# complete_system_Rev_A.net
KiCad netlist of a schematic drawn in EAGLE
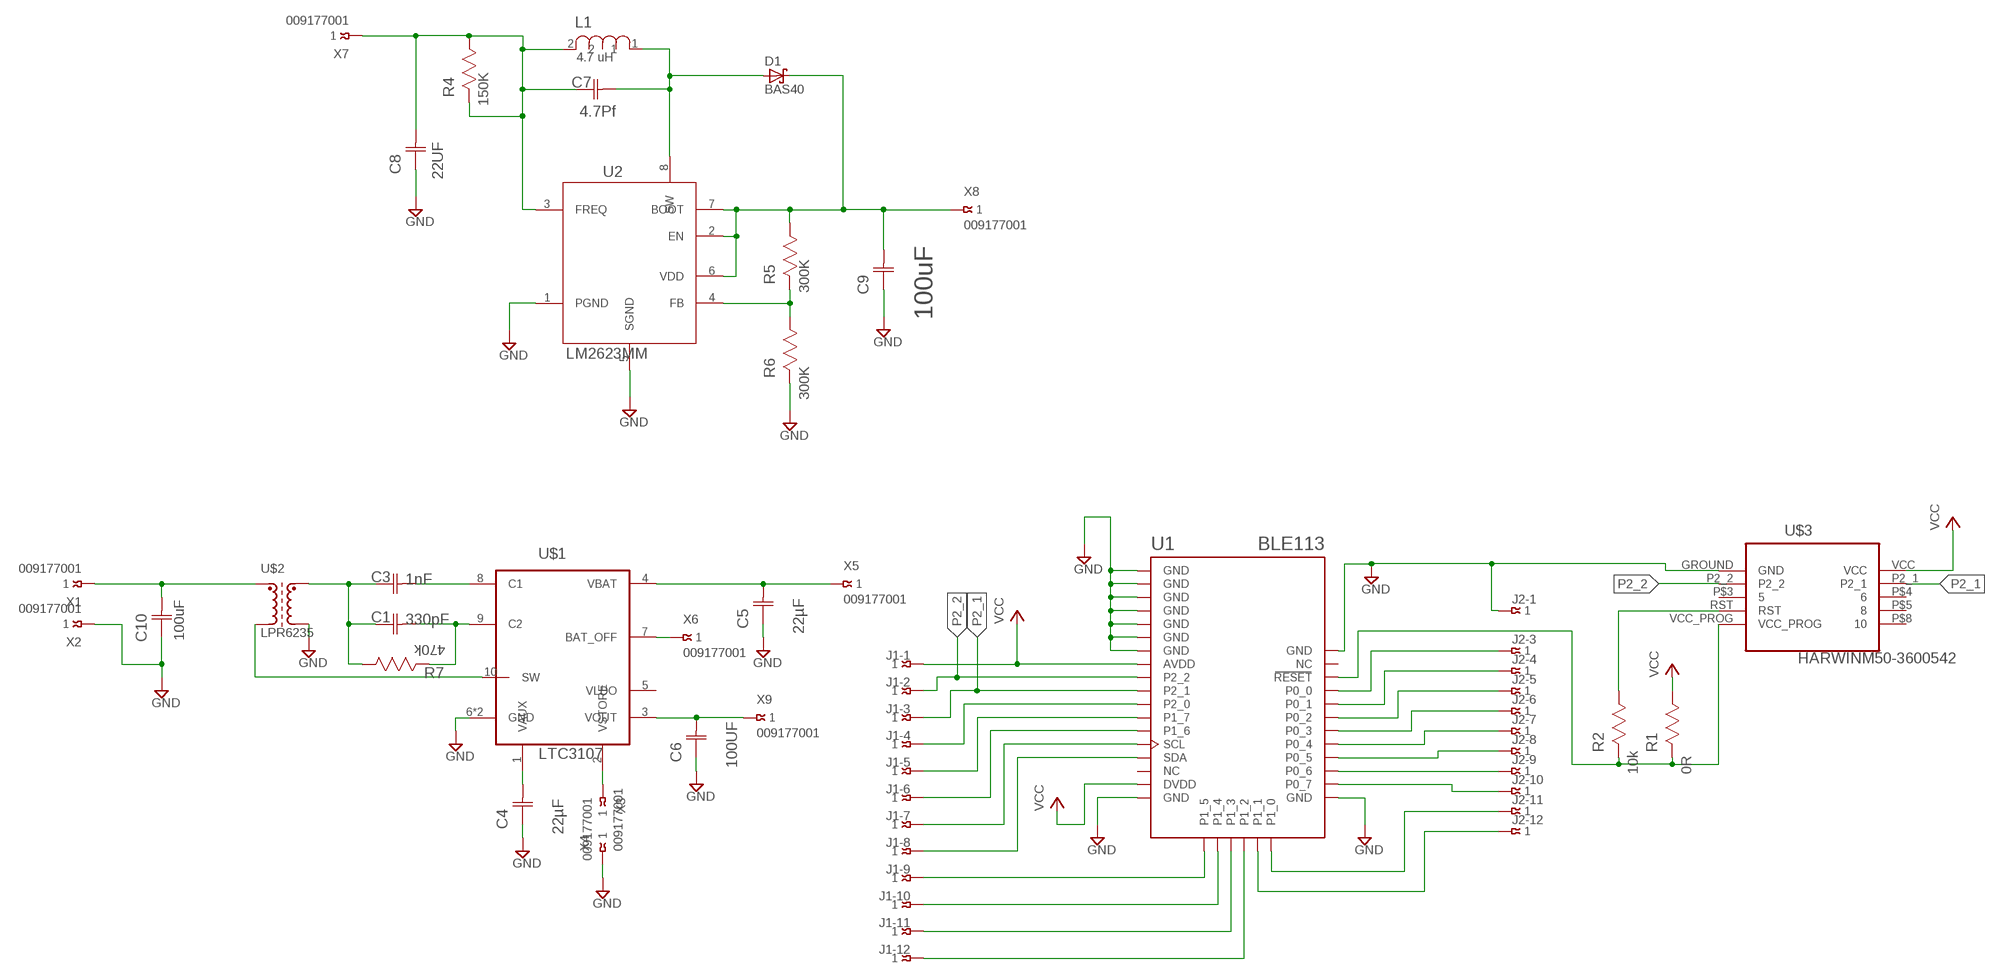
[diagram p0: schematic, sheet 1]

(export (version "E")
  (design (tool "Eeschema 10.0.6"))
  (components
    (comp (ref "C1")
      (value "330pF")
      (footprint "eagle-import:CAPC1005X60N")
      (fields (field (name "MPN") "0402YD105KAT2A") (field (name "TOLERANCE") "±10%"))
      (libsource (lib "eagle-import") (part "0402YD105KAT2A"))
    )
    (comp (ref "C3")
      (value "1nF")
      (footprint "eagle-import:CAPC1005X60N")
      (fields (field (name "MPN") "0402YD105KAT2A") (field (name "TOLERANCE") "±10%"))
      (libsource (lib "eagle-import") (part "0402YD105KAT2A"))
    )
    (comp (ref "C4")
      (value "22µF")
      (footprint "eagle-import:CAPCP3216X180N")
      (fields (field (name "MPN") "TCJA156M006R0300"))
      (libsource (lib "eagle-import") (part "TCJA156M006R0300"))
    )
    (comp (ref "C5")
      (value "22µF")
      (footprint "eagle-import:CAPCP3216X180N")
      (fields (field (name "MPN") "TCJA156M006R0300"))
      (libsource (lib "eagle-import") (part "TCJA156M006R0300"))
    )
    (comp (ref "C6")
      (value "100UF")
      (footprint "eagle-import:CAPCP3216X180N")
      (fields (field (name "MPN") "TACA107M006XTA"))
      (libsource (lib "eagle-import") (part "TACA107M006XTA"))
    )
    (comp (ref "C7")
      (value "4.7Pf")
      (footprint "eagle-import:CAPC1005X60N")
      (fields (field (name "MPN") "0402YD105KAT2A") (field (name "TOLERANCE") "±10%"))
      (libsource (lib "eagle-import") (part "0402YD105KAT2A"))
    )
    (comp (ref "C8")
      (value "22UF")
      (footprint "eagle-import:CAPC2012X94N")
      (fields (field (name "MPN") "0805YA120KAT2A") (field (name "TOLERANCE") "±10%"))
      (libsource (lib "eagle-import") (part "0805YA120KAT2A"))
    )
    (comp (ref "C9")
      (value "100uF")
      (footprint "eagle-import:CAPC3216X180N")
      (fields (field (name "MPN") "C1206C107M9PACTU") (field (name "TOLERANCE") "±20%"))
      (libsource (lib "eagle-import") (part "C1206C107M9PACTU"))
    )
    (comp (ref "C10")
      (value "100uF")
      (footprint "eagle-import:CAPC3216X180N")
      (fields (field (name "MPN") "C1206C107M9PACTU") (field (name "TOLERANCE") "±20%"))
      (libsource (lib "eagle-import") (part "C1206C107M9PACTU"))
    )
    (comp (ref "D1")
      (value "BAS40")
      (footprint "eagle-import:SOT23")
      (libsource (lib "eagle-import") (part "BAS40"))
    )
    (comp (ref "J1-1")
      (value "009177001")
      (footprint "eagle-import:009177001")
      (fields (field (name "MPN") "009177001001006"))
      (libsource (lib "eagle-import") (part "00917?0017"))
    )
    (comp (ref "J1-2")
      (value "009177001")
      (footprint "eagle-import:009177001")
      (fields (field (name "MPN") "009177001001006"))
      (libsource (lib "eagle-import") (part "00917?0017"))
    )
    (comp (ref "J1-3")
      (value "009177001")
      (footprint "eagle-import:009177001")
      (fields (field (name "MPN") "009177001001006"))
      (libsource (lib "eagle-import") (part "00917?0017"))
    )
    (comp (ref "J1-4")
      (value "009177001")
      (footprint "eagle-import:009177001")
      (fields (field (name "MPN") "009177001001006"))
      (libsource (lib "eagle-import") (part "00917?0017"))
    )
    (comp (ref "J1-5")
      (value "009177001")
      (footprint "eagle-import:009177001")
      (fields (field (name "MPN") "009177001001006"))
      (libsource (lib "eagle-import") (part "00917?0017"))
    )
    (comp (ref "J1-6")
      (value "009177001")
      (footprint "eagle-import:009177001")
      (fields (field (name "MPN") "009177001001006"))
      (libsource (lib "eagle-import") (part "00917?0017"))
    )
    (comp (ref "J1-7")
      (value "009177001")
      (footprint "eagle-import:009177001")
      (fields (field (name "MPN") "009177001001006"))
      (libsource (lib "eagle-import") (part "00917?0017"))
    )
    (comp (ref "J1-8")
      (value "009177001")
      (footprint "eagle-import:009177001")
      (fields (field (name "MPN") "009177001001006"))
      (libsource (lib "eagle-import") (part "00917?0017"))
    )
    (comp (ref "J1-9")
      (value "009177001")
      (footprint "eagle-import:009177001")
      (fields (field (name "MPN") "009177001001006"))
      (libsource (lib "eagle-import") (part "00917?0017"))
    )
    (comp (ref "J1-10")
      (value "009177001")
      (footprint "eagle-import:009177001")
      (fields (field (name "MPN") "009177001001006"))
      (libsource (lib "eagle-import") (part "00917?0017"))
    )
    (comp (ref "J1-11")
      (value "009177001")
      (footprint "eagle-import:009177001")
      (fields (field (name "MPN") "009177001001006"))
      (libsource (lib "eagle-import") (part "00917?0017"))
    )
    (comp (ref "J1-12")
      (value "009177001")
      (footprint "eagle-import:009177001")
      (fields (field (name "MPN") "009177001001006"))
      (libsource (lib "eagle-import") (part "00917?0017"))
    )
    (comp (ref "J2-1")
      (value "009177001")
      (footprint "eagle-import:009177001")
      (fields (field (name "MPN") "009177001001006"))
      (libsource (lib "eagle-import") (part "00917?0017"))
    )
    (comp (ref "J2-3")
      (value "009177001")
      (footprint "eagle-import:009177001")
      (fields (field (name "MPN") "009177001001006"))
      (libsource (lib "eagle-import") (part "00917?0017"))
    )
    (comp (ref "J2-4")
      (value "009177001")
      (footprint "eagle-import:009177001")
      (fields (field (name "MPN") "009177001001006"))
      (libsource (lib "eagle-import") (part "00917?0017"))
    )
    (comp (ref "J2-5")
      (value "009177001")
      (footprint "eagle-import:009177001")
      (fields (field (name "MPN") "009177001001006"))
      (libsource (lib "eagle-import") (part "00917?0017"))
    )
    (comp (ref "J2-6")
      (value "009177001")
      (footprint "eagle-import:009177001")
      (fields (field (name "MPN") "009177001001006"))
      (libsource (lib "eagle-import") (part "00917?0017"))
    )
    (comp (ref "J2-7")
      (value "009177001")
      (footprint "eagle-import:009177001")
      (fields (field (name "MPN") "009177001001006"))
      (libsource (lib "eagle-import") (part "00917?0017"))
    )
    (comp (ref "J2-8")
      (value "009177001")
      (footprint "eagle-import:009177001")
      (fields (field (name "MPN") "009177001001006"))
      (libsource (lib "eagle-import") (part "00917?0017"))
    )
    (comp (ref "J2-9")
      (value "009177001")
      (footprint "eagle-import:009177001")
      (fields (field (name "MPN") "009177001001006"))
      (libsource (lib "eagle-import") (part "00917?0017"))
    )
    (comp (ref "J2-10")
      (value "009177001")
      (footprint "eagle-import:009177001")
      (fields (field (name "MPN") "009177001001006"))
      (libsource (lib "eagle-import") (part "00917?0017"))
    )
    (comp (ref "J2-11")
      (value "009177001")
      (footprint "eagle-import:009177001")
      (fields (field (name "MPN") "009177001001006"))
      (libsource (lib "eagle-import") (part "00917?0017"))
    )
    (comp (ref "J2-12")
      (value "009177001")
      (footprint "eagle-import:009177001")
      (fields (field (name "MPN") "009177001001006"))
      (libsource (lib "eagle-import") (part "00917?0017"))
    )
    (comp (ref "L1")
      (value "4.7 uH")
      (footprint "eagle-import:INDC3225X22N")
      (fields (field (name "MPN") "PM1210-4R7J-RC") (field (name "TOLERANCE") "±5 %"))
      (libsource (lib "eagle-import") (part "PM1210-4R7J-RC"))
    )
    (comp (ref "R1")
      (value "0R")
      (footprint "eagle-import:RESC1005X40N")
      (fields (field (name "MPN") "CRCW0402300KFKED") (field (name "TOLERANCE") "±1%"))
      (libsource (lib "eagle-import") (part "CRCW0402300KFKED"))
    )
    (comp (ref "R2")
      (value "10k")
      (footprint "eagle-import:RESC1005X40N")
      (fields (field (name "MPN") "CRCW0402300KFKED") (field (name "TOLERANCE") "±1%"))
      (libsource (lib "eagle-import") (part "CRCW0402300KFKED"))
    )
    (comp (ref "R4")
      (value "150K")
      (footprint "eagle-import:RESC1005X40N")
      (fields (field (name "MPN") "CRCW0402150KFKED") (field (name "TOLERANCE") "±1%"))
      (libsource (lib "eagle-import") (part "CRCW0402150KFKED"))
    )
    (comp (ref "R5")
      (value "300K")
      (footprint "eagle-import:RESC1005X40N")
      (fields (field (name "MPN") "CRCW0402300KFKED") (field (name "TOLERANCE") "±1%"))
      (libsource (lib "eagle-import") (part "CRCW0402300KFKED"))
    )
    (comp (ref "R6")
      (value "300K")
      (footprint "eagle-import:RESC1005X40N")
      (fields (field (name "MPN") "CRCW0402300KFKED") (field (name "TOLERANCE") "±1%"))
      (libsource (lib "eagle-import") (part "CRCW0402300KFKED"))
    )
    (comp (ref "R7")
      (value "470k")
      (footprint "eagle-import:RESC1005X40N")
      (fields (field (name "MPN") "CRCW0402300KFKED") (field (name "TOLERANCE") "±1%"))
      (libsource (lib "eagle-import") (part "CRCW0402300KFKED"))
    )
    (comp (ref "U$1")
      (value "LTC3107")
      (footprint "eagle-import:LTC3107")
      (libsource (lib "eagle-import") (part "LTC3107"))
    )
    (comp (ref "U$2")
      (value "LPR6235")
      (footprint "eagle-import:LPR6235")
      (libsource (lib "eagle-import") (part "LPR6235"))
    )
    (comp (ref "U$3")
      (value "HARWINM50-3600542")
      (footprint "eagle-import:HARWINM50-3600542")
      (libsource (lib "eagle-import") (part "HARWINM50-3600542"))
    )
    (comp (ref "U1")
      (value "BLE113")
      (footprint "eagle-import:BLE113-A")
      (libsource (lib "eagle-import") (part "BLE113-VISUAL-A"))
    )
    (comp (ref "U2")
      (value "LM2623MM")
      (footprint "eagle-import:SOP65P490X110-8N")
      (libsource (lib "eagle-import") (part "LM2623MM"))
    )
    (comp (ref "X1")
      (value "009177001")
      (footprint "eagle-import:009177001")
      (fields (field (name "MPN") "009177001001006"))
      (libsource (lib "eagle-import") (part "00917?0017"))
    )
    (comp (ref "X2")
      (value "009177001")
      (footprint "eagle-import:009177001")
      (fields (field (name "MPN") "009177001001006"))
      (libsource (lib "eagle-import") (part "00917?0017"))
    )
    (comp (ref "X3")
      (value "009177001")
      (footprint "eagle-import:009177001")
      (fields (field (name "MPN") "009177001001006"))
      (libsource (lib "eagle-import") (part "00917?0017"))
    )
    (comp (ref "X4")
      (value "009177001")
      (footprint "eagle-import:009177001")
      (fields (field (name "MPN") "009177001001006"))
      (libsource (lib "eagle-import") (part "00917?0017"))
    )
    (comp (ref "X5")
      (value "009177001")
      (footprint "eagle-import:009177001")
      (fields (field (name "MPN") "009177001001006"))
      (libsource (lib "eagle-import") (part "00917?0017"))
    )
    (comp (ref "X6")
      (value "009177001")
      (footprint "eagle-import:009177001")
      (fields (field (name "MPN") "009177001001006"))
      (libsource (lib "eagle-import") (part "00917?0017"))
    )
    (comp (ref "X7")
      (value "009177001")
      (footprint "eagle-import:009177001")
      (fields (field (name "MPN") "009177001001006"))
      (libsource (lib "eagle-import") (part "00917?0017"))
    )
    (comp (ref "X8")
      (value "009177001")
      (footprint "eagle-import:009177001")
      (fields (field (name "MPN") "009177001001006"))
      (libsource (lib "eagle-import") (part "00917?0017"))
    )
    (comp (ref "X9")
      (value "009177001")
      (footprint "eagle-import:009177001")
      (fields (field (name "MPN") "009177001001006"))
      (libsource (lib "eagle-import") (part "00917?0017"))
    )
  )
  (nets
    (net (code "1") (name "GND") (class "Default")
      (node (ref "C10") (pin "1") (pinfunction "C1_1") (pintype "passive"))
      (node (ref "C4") (pin "1") (pinfunction "C1_1") (pintype "passive"))
      (node (ref "C5") (pin "1") (pinfunction "C1_1") (pintype "passive"))
      (node (ref "C6") (pin "1") (pinfunction "C1_1") (pintype "passive"))
      (node (ref "C8") (pin "1") (pinfunction "C1_1") (pintype "passive"))
      (node (ref "C9") (pin "1") (pinfunction "C1_1") (pintype "passive"))
      (node (ref "J2-1") (pin "1") (pinfunction "1_1") (pintype "passive"))
      (node (ref "R6") (pin "2") (pinfunction "2_2") (pintype "passive"))
      (node (ref "U$1") (pin "11") (pinfunction "GND_11") (pintype "passive"))
      (node (ref "U$1") (pin "6") (pinfunction "GND_6") (pintype "passive"))
      (node (ref "U$2") (pin "P$3") (pinfunction "OP2_P$3") (pintype "passive"))
      (node (ref "U$3") (pin "GROUND") (pinfunction "GND_GROUND") (pintype "passive"))
      (node (ref "U1") (pin "GND") (pinfunction "GND_GND") (pintype "power_in"))
      (node (ref "U1") (pin "GND@10") (pinfunction "GND_GND@10") (pintype "power_in"))
      (node (ref "U1") (pin "GND@2") (pinfunction "GND_GND@2") (pintype "power_in"))
      (node (ref "U1") (pin "GND@3") (pinfunction "GND_GND@3") (pintype "power_in"))
      (node (ref "U1") (pin "GND@4") (pinfunction "GND_GND@4") (pintype "power_in"))
      (node (ref "U1") (pin "GND@5") (pinfunction "GND_GND@5") (pintype "power_in"))
      (node (ref "U1") (pin "GND@6") (pinfunction "GND_GND@6") (pintype "power_in"))
      (node (ref "U1") (pin "GND@7") (pinfunction "GND_GND@7") (pintype "power_in"))
      (node (ref "U1") (pin "GND@8") (pinfunction "GND_GND@8") (pintype "power_in"))
      (node (ref "U1") (pin "GND@9") (pinfunction "GND_GND@9") (pintype "power_in"))
      (node (ref "U2") (pin "1") (pinfunction "PGND_1") (pintype "passive"))
      (node (ref "U2") (pin "5") (pinfunction "SGND_5") (pintype "passive"))
      (node (ref "X2") (pin "1") (pinfunction "1_1") (pintype "passive"))
      (node (ref "X4") (pin "1") (pinfunction "1_1") (pintype "passive"))
    )
    (net (code "2") (name "Net-(C1-C1)") (class "Default")
      (node (ref "C1") (pin "2") (pinfunction "C1_2") (pintype "passive"))
      (node (ref "C3") (pin "2") (pinfunction "C1_2") (pintype "passive"))
      (node (ref "R7") (pin "1") (pinfunction "1_1") (pintype "passive"))
      (node (ref "U$2") (pin "P$4") (pinfunction "OP1_P$4") (pintype "passive"))
    )
    (net (code "3") (name "Net-(C1-C2)") (class "Default")
      (node (ref "C1") (pin "1") (pinfunction "C2_1") (pintype "passive"))
      (node (ref "R7") (pin "2") (pinfunction "2_2") (pintype "passive"))
      (node (ref "U$1") (pin "9") (pinfunction "C2_9") (pintype "input"))
    )
    (net (code "4") (name "Net-(C3-C2)") (class "Default")
      (node (ref "C3") (pin "1") (pinfunction "C2_1") (pintype "passive"))
      (node (ref "U$1") (pin "8") (pinfunction "C1_8") (pintype "input"))
    )
    (net (code "5") (name "Net-(C4-C2)") (class "Default")
      (node (ref "C4") (pin "2") (pinfunction "C2_2") (pintype "passive"))
      (node (ref "U$1") (pin "1") (pinfunction "VAUX_1") (pintype "input"))
    )
    (net (code "6") (name "Net-(C5-C2)") (class "Default")
      (node (ref "C5") (pin "2") (pinfunction "C2_2") (pintype "passive"))
      (node (ref "U$1") (pin "4") (pinfunction "VBAT_4") (pintype "input"))
      (node (ref "X5") (pin "1") (pinfunction "1_1") (pintype "passive"))
    )
    (net (code "7") (name "Net-(C6-C2)") (class "Default")
      (node (ref "C6") (pin "2") (pinfunction "C2_2") (pintype "passive"))
      (node (ref "U$1") (pin "3") (pinfunction "VOUT_3") (pintype "output"))
      (node (ref "X9") (pin "1") (pinfunction "1_1") (pintype "passive"))
    )
    (net (code "8") (name "Net-(C7-C1)") (class "Default")
      (node (ref "C7") (pin "2") (pinfunction "C1_2") (pintype "passive"))
      (node (ref "C8") (pin "2") (pinfunction "C2_2") (pintype "passive"))
      (node (ref "L1") (pin "2") (pinfunction "2_2") (pintype "passive"))
      (node (ref "R4") (pin "1") (pinfunction "1_1") (pintype "passive"))
      (node (ref "R4") (pin "2") (pinfunction "2_2") (pintype "passive"))
      (node (ref "U2") (pin "3") (pinfunction "FREQ_3") (pintype "input"))
      (node (ref "X7") (pin "1") (pinfunction "1_1") (pintype "passive"))
    )
    (net (code "9") (name "Net-(C7-C2)") (class "Default")
      (node (ref "C7") (pin "1") (pinfunction "C2_1") (pintype "passive"))
      (node (ref "D1") (pin "1") (pinfunction "A_1") (pintype "passive"))
      (node (ref "L1") (pin "1") (pinfunction "1_1") (pintype "passive"))
      (node (ref "U2") (pin "8") (pinfunction "SW_8") (pintype "output"))
    )
    (net (code "10") (name "Net-(C9-C2)") (class "Default")
      (node (ref "C9") (pin "2") (pinfunction "C2_2") (pintype "passive"))
      (node (ref "D1") (pin "3") (pinfunction "C_3") (pintype "passive"))
      (node (ref "R5") (pin "1") (pinfunction "1_1") (pintype "passive"))
      (node (ref "U2") (pin "2") (pinfunction "EN_2") (pintype "input"))
      (node (ref "U2") (pin "6") (pinfunction "VDD_6") (pintype "power_in"))
      (node (ref "U2") (pin "7") (pinfunction "BOOT_7") (pintype "input"))
      (node (ref "X8") (pin "1") (pinfunction "1_1") (pintype "passive"))
    )
    (net (code "11") (name "Net-(C10-C2)") (class "Default")
      (node (ref "C10") (pin "2") (pinfunction "C2_2") (pintype "passive"))
      (node (ref "U$2") (pin "P$1") (pinfunction "IP1_P$1") (pintype "passive"))
      (node (ref "X1") (pin "1") (pinfunction "1_1") (pintype "passive"))
    )
    (net (code "12") (name "Net-(J1-4-Pad1)") (class "Default")
      (node (ref "J1-4") (pin "1") (pinfunction "1_1") (pintype "passive"))
      (node (ref "U1") (pin "P2_0") (pinfunction "P2_0_P2_0") (pintype "bidirectional"))
    )
    (net (code "13") (name "Net-(J1-5-Pad1)") (class "Default")
      (node (ref "J1-5") (pin "1") (pinfunction "1_1") (pintype "passive"))
      (node (ref "U1") (pin "P1_7") (pinfunction "P1_7_P1_7") (pintype "bidirectional"))
    )
    (net (code "14") (name "Net-(J1-6-Pad1)") (class "Default")
      (node (ref "J1-6") (pin "1") (pinfunction "1_1") (pintype "passive"))
      (node (ref "U1") (pin "P1_6") (pinfunction "P1_6_P1_6") (pintype "bidirectional"))
    )
    (net (code "15") (name "Net-(J1-7-Pad1)") (class "Default")
      (node (ref "J1-7") (pin "1") (pinfunction "1_1") (pintype "passive"))
      (node (ref "U1") (pin "SCL") (pinfunction "SCL_SCL") (pintype "bidirectional"))
    )
    (net (code "16") (name "Net-(J1-8-Pad1)") (class "Default")
      (node (ref "J1-8") (pin "1") (pinfunction "1_1") (pintype "passive"))
      (node (ref "U1") (pin "SDA") (pinfunction "SDA_SDA") (pintype "bidirectional"))
    )
    (net (code "17") (name "Net-(J1-9-Pad1)") (class "Default")
      (node (ref "J1-9") (pin "1") (pinfunction "1_1") (pintype "passive"))
      (node (ref "U1") (pin "P1_5") (pinfunction "P1_5_P1_5") (pintype "bidirectional"))
    )
    (net (code "18") (name "Net-(J1-10-Pad1)") (class "Default")
      (node (ref "J1-10") (pin "1") (pinfunction "1_1") (pintype "passive"))
      (node (ref "U1") (pin "P1_4") (pinfunction "P1_4_P1_4") (pintype "bidirectional"))
    )
    (net (code "19") (name "Net-(J1-11-Pad1)") (class "Default")
      (node (ref "J1-11") (pin "1") (pinfunction "1_1") (pintype "passive"))
      (node (ref "U1") (pin "P1_3") (pinfunction "P1_3_P1_3") (pintype "bidirectional"))
    )
    (net (code "20") (name "Net-(J1-12-Pad1)") (class "Default")
      (node (ref "J1-12") (pin "1") (pinfunction "1_1") (pintype "passive"))
      (node (ref "U1") (pin "P1_2") (pinfunction "P1_2_P1_2") (pintype "bidirectional"))
    )
    (net (code "21") (name "Net-(J2-3-Pad1)") (class "Default")
      (node (ref "J2-3") (pin "1") (pinfunction "1_1") (pintype "passive"))
      (node (ref "U1") (pin "P0_0") (pinfunction "P0_0_P0_0") (pintype "bidirectional"))
    )
    (net (code "22") (name "Net-(J2-4-Pad1)") (class "Default")
      (node (ref "J2-4") (pin "1") (pinfunction "1_1") (pintype "passive"))
      (node (ref "U1") (pin "P0_1") (pinfunction "P0_1_P0_1") (pintype "bidirectional"))
    )
    (net (code "23") (name "Net-(J2-5-Pad1)") (class "Default")
      (node (ref "J2-5") (pin "1") (pinfunction "1_1") (pintype "passive"))
      (node (ref "U1") (pin "P0_2") (pinfunction "P0_2_P0_2") (pintype "bidirectional"))
    )
    (net (code "24") (name "Net-(J2-6-Pad1)") (class "Default")
      (node (ref "J2-6") (pin "1") (pinfunction "1_1") (pintype "passive"))
      (node (ref "U1") (pin "P0_3") (pinfunction "P0_3_P0_3") (pintype "bidirectional"))
    )
    (net (code "25") (name "Net-(J2-7-Pad1)") (class "Default")
      (node (ref "J2-7") (pin "1") (pinfunction "1_1") (pintype "passive"))
      (node (ref "U1") (pin "P0_4") (pinfunction "P0_4_P0_4") (pintype "bidirectional"))
    )
    (net (code "26") (name "Net-(J2-8-Pad1)") (class "Default")
      (node (ref "J2-8") (pin "1") (pinfunction "1_1") (pintype "passive"))
      (node (ref "U1") (pin "P0_5") (pinfunction "P0_5_P0_5") (pintype "bidirectional"))
    )
    (net (code "27") (name "Net-(J2-9-Pad1)") (class "Default")
      (node (ref "J2-9") (pin "1") (pinfunction "1_1") (pintype "passive"))
      (node (ref "U1") (pin "P0_6") (pinfunction "P0_6_P0_6") (pintype "bidirectional"))
    )
    (net (code "28") (name "Net-(J2-10-Pad1)") (class "Default")
      (node (ref "J2-10") (pin "1") (pinfunction "1_1") (pintype "passive"))
      (node (ref "U1") (pin "P0_7") (pinfunction "P0_7_P0_7") (pintype "bidirectional"))
    )
    (net (code "29") (name "Net-(J2-11-Pad1)") (class "Default")
      (node (ref "J2-11") (pin "1") (pinfunction "1_1") (pintype "passive"))
      (node (ref "U1") (pin "P1_0") (pinfunction "P1_0_P1_0") (pintype "bidirectional"))
    )
    (net (code "30") (name "Net-(J2-12-Pad1)") (class "Default")
      (node (ref "J2-12") (pin "1") (pinfunction "1_1") (pintype "passive"))
      (node (ref "U1") (pin "P1_1") (pinfunction "P1_1_P1_1") (pintype "bidirectional"))
    )
    (net (code "31") (name "Net-(R1-Pad2)") (class "Default")
      (node (ref "R1") (pin "2") (pinfunction "2_2") (pintype "passive"))
      (node (ref "R2") (pin "2") (pinfunction "2_2") (pintype "passive"))
      (node (ref "U$3") (pin "VCC_PROG") (pinfunction "VCC_PROG_VCC_PROG") (pintype "passive"))
      (node (ref "U1") (pin "RESET") (pinfunction "RESET_RESET") (pintype "input"))
    )
    (net (code "32") (name "Net-(R2-Pad1)") (class "Default")
      (node (ref "R2") (pin "1") (pinfunction "1_1") (pintype "passive"))
      (node (ref "U$3") (pin "RST") (pinfunction "RST_RST") (pintype "passive"))
    )
    (net (code "33") (name "Net-(U$1-BAT_OFF)") (class "Default")
      (node (ref "U$1") (pin "7") (pinfunction "BAT_OFF_7") (pintype "output"))
      (node (ref "X6") (pin "1") (pinfunction "1_1") (pintype "passive"))
    )
    (net (code "34") (name "Net-(U$1-SW)") (class "Default")
      (node (ref "U$1") (pin "10") (pinfunction "SW_10") (pintype "bidirectional"))
      (node (ref "U$2") (pin "P$2") (pinfunction "IP2_P$2") (pintype "passive"))
    )
    (net (code "35") (name "Net-(U$1-VSTORE)") (class "Default")
      (node (ref "U$1") (pin "2") (pinfunction "VSTORE_2") (pintype "output"))
      (node (ref "X3") (pin "1") (pinfunction "1_1") (pintype "passive"))
    )
    (net (code "36") (name "Net-(U2-FB)") (class "Default")
      (node (ref "R5") (pin "2") (pinfunction "2_2") (pintype "passive"))
      (node (ref "R6") (pin "1") (pinfunction "1_1") (pintype "passive"))
      (node (ref "U2") (pin "4") (pinfunction "FB_4") (pintype "input"))
    )
    (net (code "37") (name "P2_1") (class "Default")
      (node (ref "J1-3") (pin "1") (pinfunction "1_1") (pintype "passive"))
      (node (ref "U$3") (pin "P2_1") (pinfunction "P2_1_P2_1") (pintype "passive"))
      (node (ref "U1") (pin "P2_1") (pinfunction "P2_1_P2_1") (pintype "bidirectional"))
    )
    (net (code "38") (name "P2_2") (class "Default")
      (node (ref "J1-2") (pin "1") (pinfunction "1_1") (pintype "passive"))
      (node (ref "U$3") (pin "P2_2") (pinfunction "P2_2_P2_2") (pintype "passive"))
      (node (ref "U1") (pin "P2_2") (pinfunction "P2_2_P2_2") (pintype "bidirectional"))
    )
    (net (code "39") (name "VCC") (class "Default")
      (node (ref "J1-1") (pin "1") (pinfunction "1_1") (pintype "passive"))
      (node (ref "R1") (pin "1") (pinfunction "1_1") (pintype "passive"))
      (node (ref "U$3") (pin "VCC") (pinfunction "VCC_VCC") (pintype "passive"))
      (node (ref "U1") (pin "AVDD") (pinfunction "AVDD_AVDD") (pintype "power_in"))
      (node (ref "U1") (pin "DVDD") (pinfunction "DVDD_DVDD") (pintype "power_in"))
    )
    (net (code "40") (name "unconnected-(U$1-VLDO-Pad5)") (class "Default")
      (node (ref "U$1") (pin "5") (pinfunction "VLDO_5") (pintype "output"))
    )
    (net (code "41") (name "unconnected-(U$3-5-PadP$3)") (class "Default")
      (node (ref "U$3") (pin "P$3") (pinfunction "5_P$3") (pintype "no_connect"))
    )
    (net (code "42") (name "unconnected-(U$3-6-PadP$4)") (class "Default")
      (node (ref "U$3") (pin "P$4") (pinfunction "6_P$4") (pintype "no_connect"))
    )
    (net (code "43") (name "unconnected-(U$3-8-PadP$5)") (class "Default")
      (node (ref "U$3") (pin "P$5") (pinfunction "8_P$5") (pintype "no_connect"))
    )
    (net (code "44") (name "unconnected-(U$3-10-PadP$8)") (class "Default")
      (node (ref "U$3") (pin "P$8") (pinfunction "10_P$8") (pintype "no_connect"))
    )
    (net (code "45") (name "unconnected-(U1-NC-PadNC@2)") (class "Default")
      (node (ref "U1") (pin "NC@2") (pinfunction "NC_NC@2") (pintype "no_connect"))
    )
    (net (code "46") (name "unconnected-(U1-PadNC)") (class "Default")
      (node (ref "U1") (pin "NC") (pinfunction "NC_NC") (pintype "no_connect"))
    )
  )
)
